# SCH_NFC-card_2024-04-22.net
KiCad netlist of a schematic drawn in EasyEDA
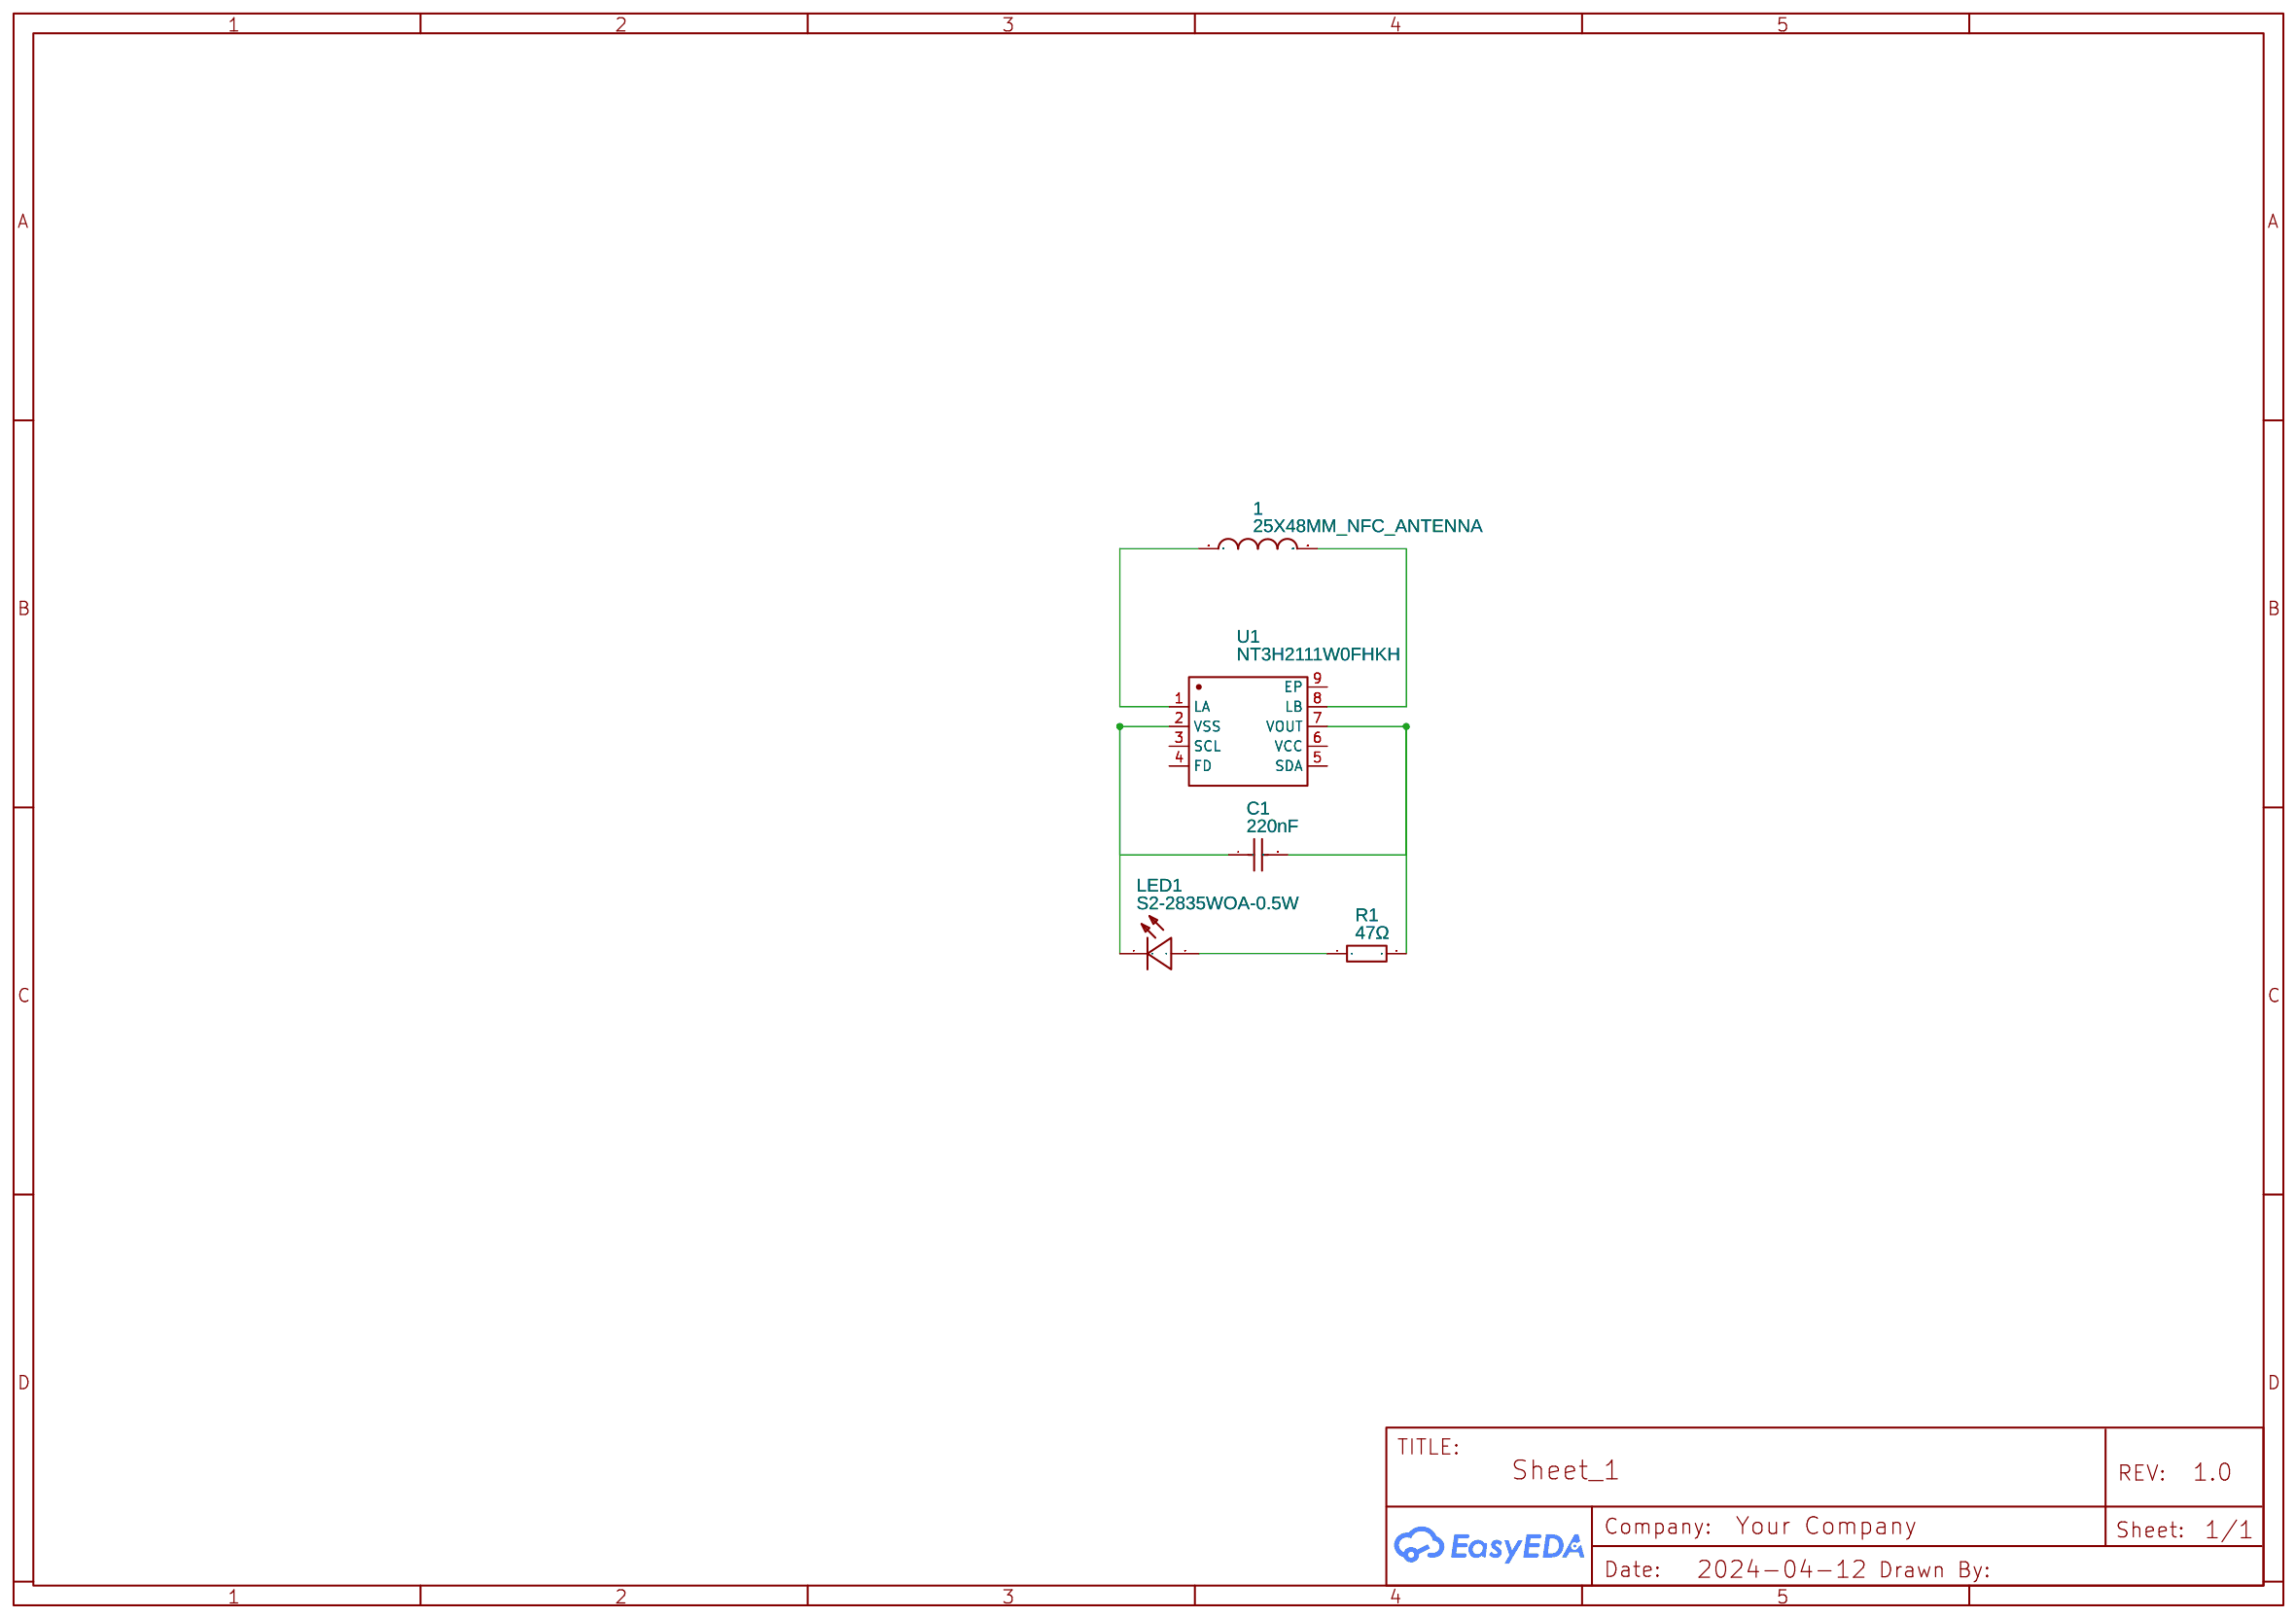
[diagram p0: schematic sheet]

(export (version "E")
  (design (tool "Eeschema 10.0.6"))
  (components
    (comp (ref "1") (value "25X48MM_NFC_ANTENNA") (libsource (lib "") (part "25X48MM_NFC_ANTENNA")))
    (comp (ref "C1")
      (value "220nF")
      (fields
        (field (name "Manufacturer Part") "GRM155R61A224KE19D")
        (field (name "Manufacturer") "muRata(村田)")
      )
      (libsource (lib "") (part "GRM155R61A224KE19D"))
    )
    (comp (ref "LED1") (value "S2-2835WOA-0.5W") (libsource (lib "") (part "S2-2835WOA-0.5W")))
    (comp (ref "R1")
      (value "47Ω")
      (fields
        (field (name "Manufacturer Part") "0603WAF470JT5E")
        (field (name "Manufacturer") "UNI-ROYAL(厚声)")
      )
      (libsource (lib "") (part "0603WAF470JT5E"))
    )
    (comp (ref "U1")
      (value "NT3H2111W0FHKH")
      (fields (field (name "Manufacturer") "NXP(恩智浦)"))
      (libsource (lib "") (part "NT3H2111W0FHKH"))
    )
  )
  (nets
    (net (code "1") (name "Net-(LED1-A)") (class "Default")
      (node (ref "LED1") (pin "2") (pinfunction "A_2") (pintype "unspecified"))
      (node (ref "R1") (pin "1") (pinfunction "1_1") (pintype "input"))
    )
    (net (code "2") (name "Net-(LED1-K)") (class "Default")
      (node (ref "C1") (pin "1") (pinfunction "1_1") (pintype "input"))
      (node (ref "LED1") (pin "1") (pinfunction "K_1") (pintype "unspecified"))
      (node (ref "U1") (pin "2") (pinfunction "VSS_2") (pintype "unspecified"))
    )
    (net (code "3") (name "Net-(U1-LA)") (class "Default")
      (node (ref "1") (pin "P$1") (pinfunction "P$1_P$1") (pintype "bidirectional"))
      (node (ref "U1") (pin "1") (pinfunction "LA_1") (pintype "unspecified"))
    )
    (net (code "4") (name "Net-(U1-LB)") (class "Default")
      (node (ref "1") (pin "P$2") (pinfunction "P$2_P$2") (pintype "bidirectional"))
      (node (ref "U1") (pin "8") (pinfunction "LB_8") (pintype "unspecified"))
    )
    (net (code "5") (name "Net-(U1-VOUT)") (class "Default")
      (node (ref "C1") (pin "2") (pinfunction "2_2") (pintype "input"))
      (node (ref "R1") (pin "2") (pinfunction "2_2") (pintype "input"))
      (node (ref "U1") (pin "7") (pinfunction "VOUT_7") (pintype "unspecified"))
    )
    (net (code "6") (name "unconnected-(U1-EP-Pad9)") (class "Default")
      (node (ref "U1") (pin "9") (pinfunction "EP_9") (pintype "unspecified"))
    )
    (net (code "7") (name "unconnected-(U1-FD-Pad4)") (class "Default")
      (node (ref "U1") (pin "4") (pinfunction "FD_4") (pintype "unspecified"))
    )
    (net (code "8") (name "unconnected-(U1-SCL-Pad3)") (class "Default")
      (node (ref "U1") (pin "3") (pinfunction "SCL_3") (pintype "unspecified"))
    )
    (net (code "9") (name "unconnected-(U1-SDA-Pad5)") (class "Default")
      (node (ref "U1") (pin "5") (pinfunction "SDA_5") (pintype "unspecified"))
    )
    (net (code "10") (name "unconnected-(U1-VCC-Pad6)") (class "Default")
      (node (ref "U1") (pin "6") (pinfunction "VCC_6") (pintype "unspecified"))
    )
  )
)
